# Sch_Buzzer.net
KiCad netlist of a schematic drawn in Altium Designer
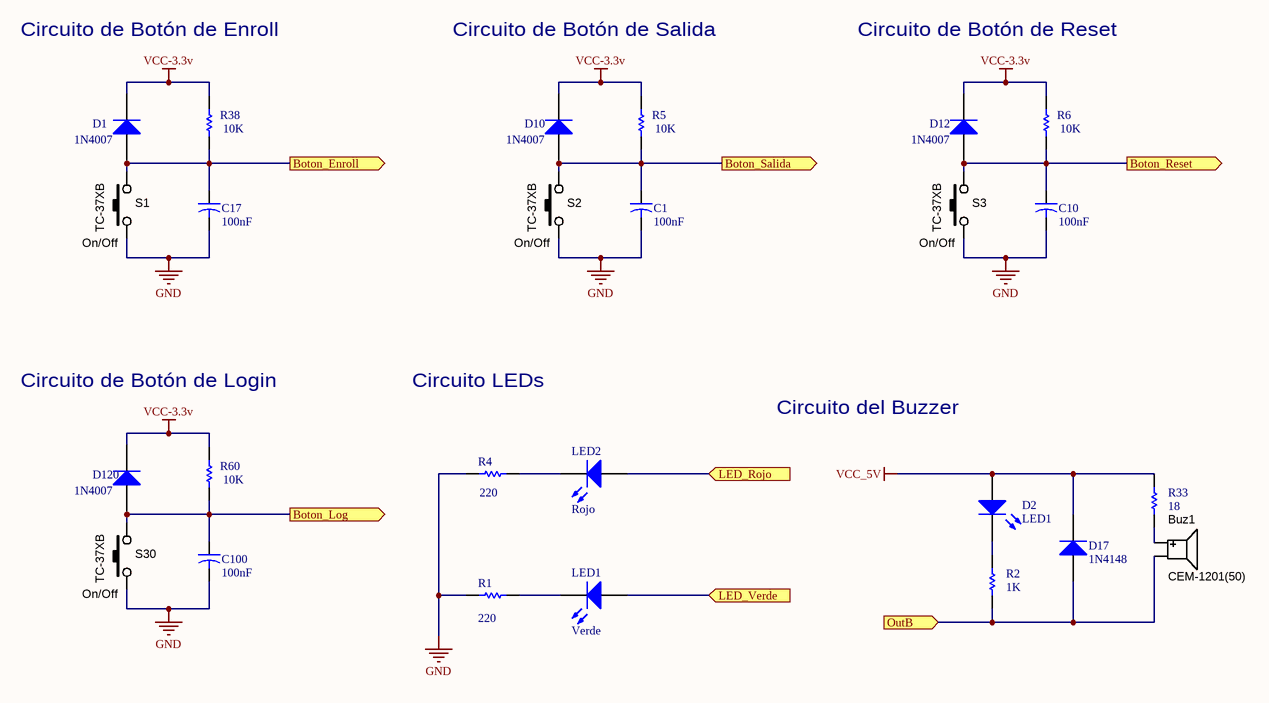
[diagram p0: Sch_Buzzer.SchDoc]

(export (version "E")
  (design (tool "Eeschema 10.0.6"))
  (components
    (comp (ref "Buz1")
      (value "Alternate part: 3100-932")
      (footprint "BUZZER_12.0X8.5MM")
      (description "Speaker, Magnetic Transducer")
      (fields (field (name "MANUFACTURER PART NUMBER 1") "CEM-1201(50)"))
      (libsource (lib "PBL - Electromechanical") (part "BZ_12x8.5x6.5_2kHz"))
    )
    (comp (ref "C1")
      (value "100nF")
      (footprint "CAPR5-4X5")
      (description "Capacitor")
      (fields (field (name "Comment") "Cap2") (field (name "PUBLISHER") "Altium Limited"))
      (libsource (lib "Miscellaneous Devices") (part "Cap2"))
    )
    (comp (ref "C10")
      (value "100nF")
      (footprint "CAPR5-4X5")
      (description "Capacitor")
      (fields (field (name "Comment") "Cap2") (field (name "PUBLISHER") "Altium Limited"))
      (libsource (lib "Miscellaneous Devices") (part "Cap2"))
    )
    (comp (ref "C17")
      (value "100nF")
      (footprint "CAPR5-4X5")
      (description "Capacitor")
      (fields (field (name "Comment") "Cap2") (field (name "PUBLISHER") "Altium Limited"))
      (libsource (lib "Miscellaneous Devices") (part "Cap2"))
    )
    (comp (ref "C100")
      (value "100nF")
      (footprint "CAPR5-4X5")
      (description "Capacitor")
      (fields (field (name "Comment") "Cap2") (field (name "PUBLISHER") "Altium Limited"))
      (libsource (lib "Miscellaneous Devices") (part "Cap2"))
    )
    (comp (ref "D1")
      (value "1N4007")
      (footprint "DO-41")
      (description "1 Amp General Purpose Rectifier")
      (fields (field (name "PUBLISHER") "Altium Limited"))
      (libsource (lib "Miscellaneous Devices") (part "Diode 1N4007"))
    )
    (comp (ref "D2")
      (value "LED1")
      (footprint "Type 3mm")
      (description "THT LED round mono-color color lens, WL-TMRW, Super Red")
      (fields (field (name "PARTNUMBER") "151031SS06000") (field (name "MANUFACTURER") "Wuerth Elektronik"))
      (libsource (lib "Altium Content Vault") (part "WE-LED_K1A2-2"))
    )
    (comp (ref "D10")
      (value "1N4007")
      (footprint "DO-41")
      (description "1 Amp General Purpose Rectifier")
      (fields (field (name "PUBLISHER") "Altium Limited"))
      (libsource (lib "Miscellaneous Devices") (part "Diode 1N4007"))
    )
    (comp (ref "D12")
      (value "1N4007")
      (footprint "DO-41")
      (description "1 Amp General Purpose Rectifier")
      (fields (field (name "PUBLISHER") "Altium Limited"))
      (libsource (lib "Miscellaneous Devices") (part "Diode 1N4007"))
    )
    (comp (ref "D17")
      (value "1N4148")
      (footprint "DO-35")
      (description "High Conductance Fast Diode")
      (fields (field (name "PUBLISHER") "Altium Limited"))
      (libsource (lib "Miscellaneous Devices") (part "Diode 1N4148"))
    )
    (comp (ref "D120")
      (value "1N4007")
      (footprint "DO-41")
      (description "1 Amp General Purpose Rectifier")
      (fields (field (name "PUBLISHER") "Altium Limited"))
      (libsource (lib "Miscellaneous Devices") (part "Diode 1N4007"))
    )
    (comp (ref "LED1")
      (value "Verde")
      (footprint "Type 5mm")
      (description "THT LED round mono-color waterclear, WL-TMRW, Green")
      (fields (field (name "PARTNUMBER") "151053GS03000") (field (name "MANUFACTURER") "Wuerth Elektronik"))
      (libsource (lib "Altium Content Vault") (part "WE-LED_K1A2-2"))
    )
    (comp (ref "LED2")
      (value "Rojo")
      (footprint "Type 5mm")
      (description "THT LED round mono-color color lens, WL-TMRW, Red")
      (fields (field (name "PARTNUMBER") "151051RS11000") (field (name "MANUFACTURER") "Wuerth Elektronik"))
      (libsource (lib "Altium Content Vault") (part "CMP-1488-00008-1"))
    )
    (comp (ref "R1")
      (value "220")
      (footprint "AXIAL-0.3")
      (description "Resistor")
      (fields (field (name "Comment") "Res1") (field (name "PUBLISHER") "Altium Limited"))
      (libsource (lib "Miscellaneous Devices") (part "Res1"))
    )
    (comp (ref "R2")
      (value "1K")
      (footprint "AXIAL-0.3")
      (description "Resistor")
      (fields (field (name "Comment") "Res1") (field (name "PUBLISHER") "Altium Limited"))
      (libsource (lib "Miscellaneous Devices") (part "Res1"))
    )
    (comp (ref "R4")
      (value "220")
      (footprint "AXIAL-0.3")
      (description "Resistor")
      (fields (field (name "Comment") "Res1") (field (name "PUBLISHER") "Altium Limited"))
      (libsource (lib "Miscellaneous Devices") (part "Res1"))
    )
    (comp (ref "R5")
      (value "10K")
      (footprint "AXIAL-0.3")
      (description "Resistor")
      (fields (field (name "Comment") "Res1") (field (name "PUBLISHER") "Altium Limited"))
      (libsource (lib "Miscellaneous Devices") (part "Res1"))
    )
    (comp (ref "R6")
      (value "10K")
      (footprint "AXIAL-0.3")
      (description "Resistor")
      (fields (field (name "Comment") "Res1") (field (name "PUBLISHER") "Altium Limited"))
      (libsource (lib "Miscellaneous Devices") (part "Res1"))
    )
    (comp (ref "R33")
      (value "18")
      (footprint "AXIAL-0.3")
      (description "Resistor")
      (fields (field (name "Comment") "Res1") (field (name "PUBLISHER") "Altium Limited"))
      (libsource (lib "Miscellaneous Devices") (part "Res1"))
    )
    (comp (ref "R38")
      (value "10K")
      (footprint "AXIAL-0.3")
      (description "Resistor")
      (fields (field (name "Comment") "Res1") (field (name "PUBLISHER") "Altium Limited"))
      (libsource (lib "Miscellaneous Devices") (part "Res1"))
    )
    (comp (ref "R60")
      (value "10K")
      (footprint "AXIAL-0.3")
      (description "Resistor")
      (fields (field (name "Comment") "Res1") (field (name "PUBLISHER") "Altium Limited"))
      (libsource (lib "Miscellaneous Devices") (part "Res1"))
    )
    (comp (ref "S1")
      (value "SW_THT_PB_5.0mm")
      (footprint "TACT-SWITCH-TC-37XB")
      (description "Switch, tact, 5.0mm stem")
      (fields (field (name "MANUFACTURER PART NUMBER 1") "TC-37XB") (field (name "FUNCTION") "On/Off"))
      (libsource (lib "PBL - Switches") (part "SW_THT_PB_5.0mm"))
    )
    (comp (ref "S2")
      (value "SW_THT_PB_5.0mm")
      (footprint "TACT-SWITCH-TC-37XB")
      (description "Switch, tact, 5.0mm stem")
      (fields (field (name "MANUFACTURER PART NUMBER 1") "TC-37XB") (field (name "FUNCTION") "On/Off"))
      (libsource (lib "PBL - Switches") (part "SW_THT_PB_5.0mm"))
    )
    (comp (ref "S3")
      (value "SW_THT_PB_5.0mm")
      (footprint "TACT-SWITCH-TC-37XB")
      (description "Switch, tact, 5.0mm stem")
      (fields (field (name "MANUFACTURER PART NUMBER 1") "TC-37XB") (field (name "FUNCTION") "On/Off"))
      (libsource (lib "PBL - Switches") (part "SW_THT_PB_5.0mm"))
    )
    (comp (ref "S30")
      (value "SW_THT_PB_5.0mm")
      (footprint "TACT-SWITCH-TC-37XB")
      (description "Switch, tact, 5.0mm stem")
      (fields (field (name "MANUFACTURER PART NUMBER 1") "TC-37XB") (field (name "FUNCTION") "On/Off"))
      (libsource (lib "PBL - Switches") (part "SW_THT_PB_5.0mm"))
    )
  )
  (nets
    (net (code "1") (name "/Boton_Enroll") (class "Default")
      (node (ref "C17") (pin "1") (pinfunction "1_1") (pintype "passive"))
      (node (ref "D1") (pin "1") (pinfunction "A_1") (pintype "passive"))
      (node (ref "R38") (pin "1") (pinfunction "1_1") (pintype "passive"))
      (node (ref "S1") (pin "2") (pintype "passive"))
    )
    (net (code "2") (name "/Boton_Log") (class "Default")
      (node (ref "C100") (pin "1") (pinfunction "1_1") (pintype "passive"))
      (node (ref "D120") (pin "1") (pinfunction "A_1") (pintype "passive"))
      (node (ref "R60") (pin "1") (pinfunction "1_1") (pintype "passive"))
      (node (ref "S30") (pin "2") (pintype "passive"))
    )
    (net (code "3") (name "/Boton_Reset") (class "Default")
      (node (ref "C10") (pin "1") (pinfunction "1_1") (pintype "passive"))
      (node (ref "D12") (pin "1") (pinfunction "A_1") (pintype "passive"))
      (node (ref "R6") (pin "1") (pinfunction "1_1") (pintype "passive"))
      (node (ref "S3") (pin "2") (pintype "passive"))
    )
    (net (code "4") (name "/Boton_Salida") (class "Default")
      (node (ref "C1") (pin "1") (pinfunction "1_1") (pintype "passive"))
      (node (ref "D10") (pin "1") (pinfunction "A_1") (pintype "passive"))
      (node (ref "R5") (pin "1") (pinfunction "1_1") (pintype "passive"))
      (node (ref "S2") (pin "2") (pintype "passive"))
    )
    (net (code "5") (name "/LED_Rojo") (class "Default")
      (node (ref "LED2") (pin "2") (pinfunction "A_2") (pintype "passive"))
    )
    (net (code "6") (name "/LED_Verde") (class "Default")
      (node (ref "LED1") (pin "2") (pinfunction "A_2") (pintype "passive"))
    )
    (net (code "7") (name "/OutB") (class "Default")
      (node (ref "Buz1") (pin "2") (pinfunction "Negative_2") (pintype "passive"))
      (node (ref "D17") (pin "1") (pinfunction "A_1") (pintype "passive"))
      (node (ref "R2") (pin "1") (pinfunction "1_1") (pintype "passive"))
    )
    (net (code "8") (name "GND") (class "Default")
      (node (ref "C1") (pin "2") (pinfunction "2_2") (pintype "passive"))
      (node (ref "C10") (pin "2") (pinfunction "2_2") (pintype "passive"))
      (node (ref "C100") (pin "2") (pinfunction "2_2") (pintype "passive"))
      (node (ref "C17") (pin "2") (pinfunction "2_2") (pintype "passive"))
      (node (ref "R1") (pin "1") (pinfunction "1_1") (pintype "passive"))
      (node (ref "R4") (pin "1") (pinfunction "1_1") (pintype "passive"))
      (node (ref "S1") (pin "1") (pintype "passive"))
      (node (ref "S2") (pin "1") (pintype "passive"))
      (node (ref "S3") (pin "1") (pintype "passive"))
      (node (ref "S30") (pin "1") (pintype "passive"))
    )
    (net (code "9") (name "Net-(Buz1-Positive)") (class "Default")
      (node (ref "Buz1") (pin "1") (pinfunction "Positive_1") (pintype "passive"))
      (node (ref "R33") (pin "1") (pinfunction "1_1") (pintype "passive"))
    )
    (net (code "10") (name "Net-(D2-K)") (class "Default")
      (node (ref "D2") (pin "1") (pinfunction "K_1") (pintype "passive"))
      (node (ref "R2") (pin "2") (pinfunction "2_2") (pintype "passive"))
    )
    (net (code "11") (name "Net-(LED1-K)") (class "Default")
      (node (ref "LED1") (pin "1") (pinfunction "K_1") (pintype "passive"))
      (node (ref "R1") (pin "2") (pinfunction "2_2") (pintype "passive"))
    )
    (net (code "12") (name "Net-(LED2-K)") (class "Default")
      (node (ref "LED2") (pin "1") (pinfunction "K_1") (pintype "passive"))
      (node (ref "R4") (pin "2") (pinfunction "2_2") (pintype "passive"))
    )
    (net (code "13") (name "VCC-3.3v") (class "Default")
      (node (ref "D1") (pin "2") (pinfunction "K_2") (pintype "passive"))
      (node (ref "D10") (pin "2") (pinfunction "K_2") (pintype "passive"))
      (node (ref "D12") (pin "2") (pinfunction "K_2") (pintype "passive"))
      (node (ref "D120") (pin "2") (pinfunction "K_2") (pintype "passive"))
      (node (ref "R38") (pin "2") (pinfunction "2_2") (pintype "passive"))
      (node (ref "R5") (pin "2") (pinfunction "2_2") (pintype "passive"))
      (node (ref "R6") (pin "2") (pinfunction "2_2") (pintype "passive"))
      (node (ref "R60") (pin "2") (pinfunction "2_2") (pintype "passive"))
    )
    (net (code "14") (name "VCC_5V") (class "Default")
      (node (ref "D17") (pin "2") (pinfunction "K_2") (pintype "passive"))
      (node (ref "D2") (pin "2") (pinfunction "A_2") (pintype "passive"))
      (node (ref "R33") (pin "2") (pinfunction "2_2") (pintype "passive"))
    )
  )
)
